# EIB64-ST4-FB-LSplit.net
KiCad netlist of a schematic drawn in EAGLE
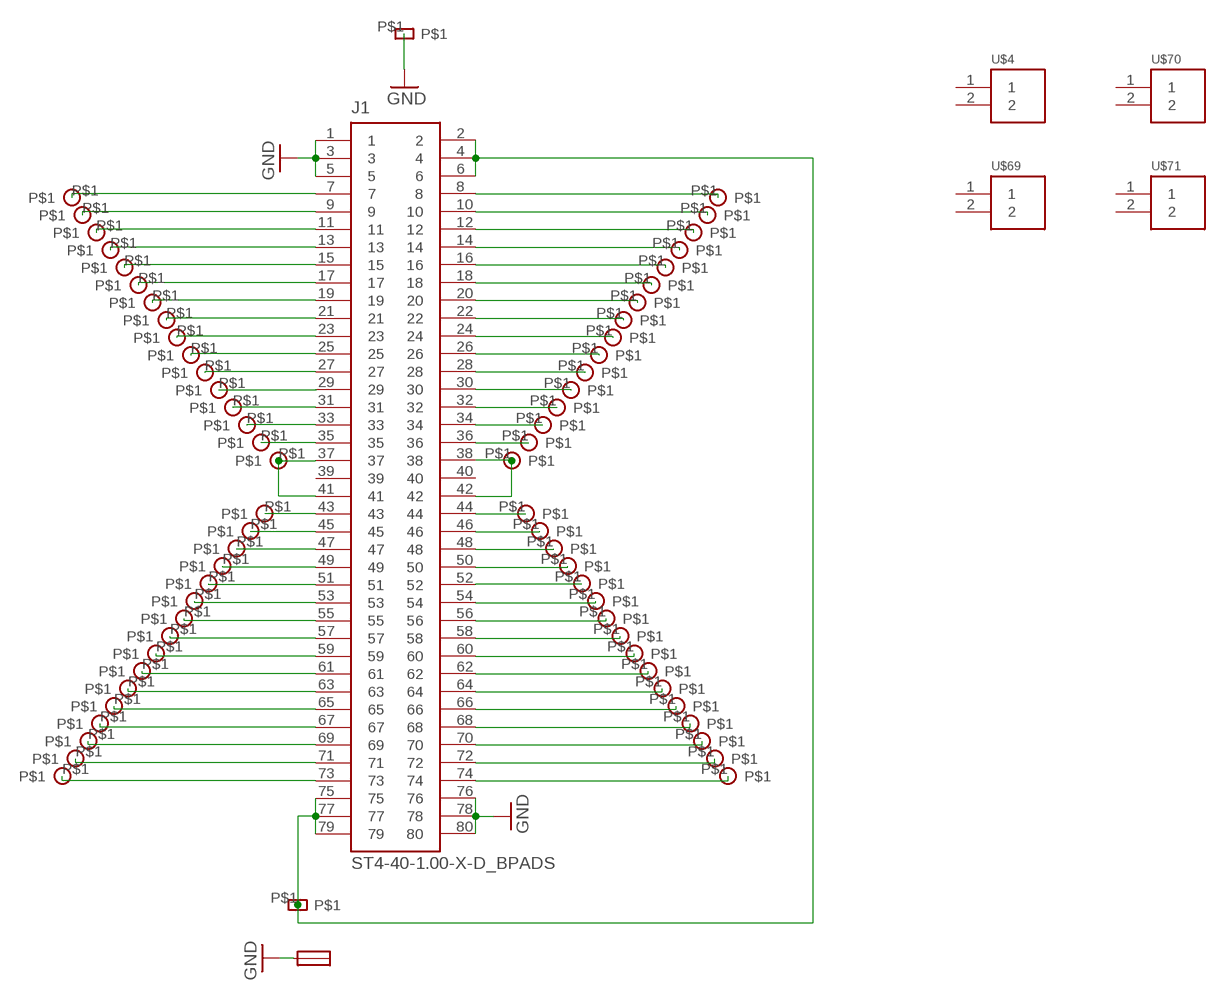
[diagram p0: schematic, sheet 1]

(export (version "E")
  (design (tool "Eeschema 10.0.6"))
  (components
    (comp (ref "J1")
      (value "ST4-40-1.00-X-D_BPADS")
      (footprint "eagle-import:ST4-40-1.00-X-D_BPADS")
      (libsource (lib "eagle-import") (part "ST4-40-1.00-X-D_BPADS"))
    )
    (comp (ref "U$1")
      (value "EIB-GND-HOLE-PAD-SMALL")
      (footprint "eagle-import:EIB-GND-HOLE-PAD-SMALL")
      (libsource (lib "eagle-import") (part "EIB-GND-HOLE-PAD-SMALL"))
    )
    (comp (ref "U$2")
      (value "JMP-PAD-SMALL")
      (footprint "eagle-import:JMP-PAD-SMALL")
      (libsource (lib "eagle-import") (part "JMP-PAD-SMALL"))
    )
    (comp (ref "U$3")
      (value "EIB-GND-HOLE-PAD-SMALL")
      (footprint "eagle-import:EIB-GND-HOLE-PAD-SMALL")
      (libsource (lib "eagle-import") (part "EIB-GND-HOLE-PAD-SMALL"))
    )
    (comp (ref "U$4")
      (value "THCONLY_TMS-102-XX-XX-S")
      (footprint "eagle-import:THCONLY_TMS-102-XX-XX-S")
      (libsource (lib "eagle-import") (part "THCONLY_TMS-102-XX-XX-S"))
    )
    (comp (ref "U$5")
      (value "EIB-TETRODE-HOLE-RS-PAD")
      (footprint "eagle-import:EIB-TETRODE-HOLE-RS-PAD")
      (libsource (lib "eagle-import") (part "EIB-TETRODE-HOLE-RS-PAD"))
    )
    (comp (ref "U$6")
      (value "EIB-TETRODE-HOLE-RS-PAD")
      (footprint "eagle-import:EIB-TETRODE-HOLE-RS-PAD")
      (libsource (lib "eagle-import") (part "EIB-TETRODE-HOLE-RS-PAD"))
    )
    (comp (ref "U$7")
      (value "EIB-TETRODE-HOLE-RS-PAD")
      (footprint "eagle-import:EIB-TETRODE-HOLE-RS-PAD")
      (libsource (lib "eagle-import") (part "EIB-TETRODE-HOLE-RS-PAD"))
    )
    (comp (ref "U$8")
      (value "EIB-TETRODE-HOLE-RS-PAD")
      (footprint "eagle-import:EIB-TETRODE-HOLE-RS-PAD")
      (libsource (lib "eagle-import") (part "EIB-TETRODE-HOLE-RS-PAD"))
    )
    (comp (ref "U$9")
      (value "EIB-TETRODE-HOLE-RS-PAD")
      (footprint "eagle-import:EIB-TETRODE-HOLE-RS-PAD")
      (libsource (lib "eagle-import") (part "EIB-TETRODE-HOLE-RS-PAD"))
    )
    (comp (ref "U$10")
      (value "EIB-TETRODE-HOLE-RS-PAD")
      (footprint "eagle-import:EIB-TETRODE-HOLE-RS-PAD")
      (libsource (lib "eagle-import") (part "EIB-TETRODE-HOLE-RS-PAD"))
    )
    (comp (ref "U$11")
      (value "EIB-TETRODE-HOLE-RS-PAD")
      (footprint "eagle-import:EIB-TETRODE-HOLE-RS-PAD")
      (libsource (lib "eagle-import") (part "EIB-TETRODE-HOLE-RS-PAD"))
    )
    (comp (ref "U$12")
      (value "EIB-TETRODE-HOLE-RS-PAD")
      (footprint "eagle-import:EIB-TETRODE-HOLE-RS-PAD")
      (libsource (lib "eagle-import") (part "EIB-TETRODE-HOLE-RS-PAD"))
    )
    (comp (ref "U$13")
      (value "EIB-TETRODE-HOLE-RS-PAD")
      (footprint "eagle-import:EIB-TETRODE-HOLE-RS-PAD")
      (libsource (lib "eagle-import") (part "EIB-TETRODE-HOLE-RS-PAD"))
    )
    (comp (ref "U$14")
      (value "EIB-TETRODE-HOLE-RS-PAD")
      (footprint "eagle-import:EIB-TETRODE-HOLE-RS-PAD")
      (libsource (lib "eagle-import") (part "EIB-TETRODE-HOLE-RS-PAD"))
    )
    (comp (ref "U$15")
      (value "EIB-TETRODE-HOLE-RS-PAD")
      (footprint "eagle-import:EIB-TETRODE-HOLE-RS-PAD")
      (libsource (lib "eagle-import") (part "EIB-TETRODE-HOLE-RS-PAD"))
    )
    (comp (ref "U$16")
      (value "EIB-TETRODE-HOLE-RS-PAD")
      (footprint "eagle-import:EIB-TETRODE-HOLE-RS-PAD")
      (libsource (lib "eagle-import") (part "EIB-TETRODE-HOLE-RS-PAD"))
    )
    (comp (ref "U$17")
      (value "EIB-TETRODE-HOLE-RS-PAD")
      (footprint "eagle-import:EIB-TETRODE-HOLE-RS-PAD")
      (libsource (lib "eagle-import") (part "EIB-TETRODE-HOLE-RS-PAD"))
    )
    (comp (ref "U$18")
      (value "EIB-TETRODE-HOLE-RS-PAD")
      (footprint "eagle-import:EIB-TETRODE-HOLE-RS-PAD")
      (libsource (lib "eagle-import") (part "EIB-TETRODE-HOLE-RS-PAD"))
    )
    (comp (ref "U$19")
      (value "EIB-TETRODE-HOLE-RS-PAD")
      (footprint "eagle-import:EIB-TETRODE-HOLE-RS-PAD")
      (libsource (lib "eagle-import") (part "EIB-TETRODE-HOLE-RS-PAD"))
    )
    (comp (ref "U$20")
      (value "EIB-TETRODE-HOLE-RS-PAD")
      (footprint "eagle-import:EIB-TETRODE-HOLE-RS-PAD")
      (libsource (lib "eagle-import") (part "EIB-TETRODE-HOLE-RS-PAD"))
    )
    (comp (ref "U$21")
      (value "EIB-TETRODE-HOLE-RS-PAD")
      (footprint "eagle-import:EIB-TETRODE-HOLE-RS-PAD")
      (libsource (lib "eagle-import") (part "EIB-TETRODE-HOLE-RS-PAD"))
    )
    (comp (ref "U$22")
      (value "EIB-TETRODE-HOLE-RS-PAD")
      (footprint "eagle-import:EIB-TETRODE-HOLE-RS-PAD")
      (libsource (lib "eagle-import") (part "EIB-TETRODE-HOLE-RS-PAD"))
    )
    (comp (ref "U$23")
      (value "EIB-TETRODE-HOLE-RS-PAD")
      (footprint "eagle-import:EIB-TETRODE-HOLE-RS-PAD")
      (libsource (lib "eagle-import") (part "EIB-TETRODE-HOLE-RS-PAD"))
    )
    (comp (ref "U$24")
      (value "EIB-TETRODE-HOLE-RS-PAD")
      (footprint "eagle-import:EIB-TETRODE-HOLE-RS-PAD")
      (libsource (lib "eagle-import") (part "EIB-TETRODE-HOLE-RS-PAD"))
    )
    (comp (ref "U$25")
      (value "EIB-TETRODE-HOLE-RS-PAD")
      (footprint "eagle-import:EIB-TETRODE-HOLE-RS-PAD")
      (libsource (lib "eagle-import") (part "EIB-TETRODE-HOLE-RS-PAD"))
    )
    (comp (ref "U$26")
      (value "EIB-TETRODE-HOLE-RS-PAD")
      (footprint "eagle-import:EIB-TETRODE-HOLE-RS-PAD")
      (libsource (lib "eagle-import") (part "EIB-TETRODE-HOLE-RS-PAD"))
    )
    (comp (ref "U$27")
      (value "EIB-TETRODE-HOLE-RS-PAD")
      (footprint "eagle-import:EIB-TETRODE-HOLE-RS-PAD")
      (libsource (lib "eagle-import") (part "EIB-TETRODE-HOLE-RS-PAD"))
    )
    (comp (ref "U$28")
      (value "EIB-TETRODE-HOLE-RS-PAD")
      (footprint "eagle-import:EIB-TETRODE-HOLE-RS-PAD")
      (libsource (lib "eagle-import") (part "EIB-TETRODE-HOLE-RS-PAD"))
    )
    (comp (ref "U$29")
      (value "EIB-TETRODE-HOLE-RS-PAD")
      (footprint "eagle-import:EIB-TETRODE-HOLE-RS-PAD")
      (libsource (lib "eagle-import") (part "EIB-TETRODE-HOLE-RS-PAD"))
    )
    (comp (ref "U$30")
      (value "EIB-TETRODE-HOLE-RS-PAD")
      (footprint "eagle-import:EIB-TETRODE-HOLE-RS-PAD")
      (libsource (lib "eagle-import") (part "EIB-TETRODE-HOLE-RS-PAD"))
    )
    (comp (ref "U$31")
      (value "EIB-TETRODE-HOLE-RS-PAD")
      (footprint "eagle-import:EIB-TETRODE-HOLE-RS-PAD")
      (libsource (lib "eagle-import") (part "EIB-TETRODE-HOLE-RS-PAD"))
    )
    (comp (ref "U$32")
      (value "EIB-TETRODE-HOLE-RS-PAD")
      (footprint "eagle-import:EIB-TETRODE-HOLE-RS-PAD")
      (libsource (lib "eagle-import") (part "EIB-TETRODE-HOLE-RS-PAD"))
    )
    (comp (ref "U$33")
      (value "EIB-TETRODE-HOLE-RS-PAD")
      (footprint "eagle-import:EIB-TETRODE-HOLE-RS-PAD")
      (libsource (lib "eagle-import") (part "EIB-TETRODE-HOLE-RS-PAD"))
    )
    (comp (ref "U$34")
      (value "EIB-TETRODE-HOLE-RS-PAD")
      (footprint "eagle-import:EIB-TETRODE-HOLE-RS-PAD")
      (libsource (lib "eagle-import") (part "EIB-TETRODE-HOLE-RS-PAD"))
    )
    (comp (ref "U$35")
      (value "EIB-TETRODE-HOLE-RS-PAD")
      (footprint "eagle-import:EIB-TETRODE-HOLE-RS-PAD")
      (libsource (lib "eagle-import") (part "EIB-TETRODE-HOLE-RS-PAD"))
    )
    (comp (ref "U$36")
      (value "EIB-TETRODE-HOLE-RS-PAD")
      (footprint "eagle-import:EIB-TETRODE-HOLE-RS-PAD")
      (libsource (lib "eagle-import") (part "EIB-TETRODE-HOLE-RS-PAD"))
    )
    (comp (ref "U$37")
      (value "EIB-TETRODE-HOLE-RS-PAD")
      (footprint "eagle-import:EIB-TETRODE-HOLE-RS-PAD")
      (libsource (lib "eagle-import") (part "EIB-TETRODE-HOLE-RS-PAD"))
    )
    (comp (ref "U$38")
      (value "EIB-TETRODE-HOLE-RS-PAD")
      (footprint "eagle-import:EIB-TETRODE-HOLE-RS-PAD")
      (libsource (lib "eagle-import") (part "EIB-TETRODE-HOLE-RS-PAD"))
    )
    (comp (ref "U$39")
      (value "EIB-TETRODE-HOLE-RS-PAD")
      (footprint "eagle-import:EIB-TETRODE-HOLE-RS-PAD")
      (libsource (lib "eagle-import") (part "EIB-TETRODE-HOLE-RS-PAD"))
    )
    (comp (ref "U$40")
      (value "EIB-TETRODE-HOLE-RS-PAD")
      (footprint "eagle-import:EIB-TETRODE-HOLE-RS-PAD")
      (libsource (lib "eagle-import") (part "EIB-TETRODE-HOLE-RS-PAD"))
    )
    (comp (ref "U$41")
      (value "EIB-TETRODE-HOLE-RS-PAD")
      (footprint "eagle-import:EIB-TETRODE-HOLE-RS-PAD")
      (libsource (lib "eagle-import") (part "EIB-TETRODE-HOLE-RS-PAD"))
    )
    (comp (ref "U$42")
      (value "EIB-TETRODE-HOLE-RS-PAD")
      (footprint "eagle-import:EIB-TETRODE-HOLE-RS-PAD")
      (libsource (lib "eagle-import") (part "EIB-TETRODE-HOLE-RS-PAD"))
    )
    (comp (ref "U$43")
      (value "EIB-TETRODE-HOLE-RS-PAD")
      (footprint "eagle-import:EIB-TETRODE-HOLE-RS-PAD")
      (libsource (lib "eagle-import") (part "EIB-TETRODE-HOLE-RS-PAD"))
    )
    (comp (ref "U$44")
      (value "EIB-TETRODE-HOLE-RS-PAD")
      (footprint "eagle-import:EIB-TETRODE-HOLE-RS-PAD")
      (libsource (lib "eagle-import") (part "EIB-TETRODE-HOLE-RS-PAD"))
    )
    (comp (ref "U$45")
      (value "EIB-TETRODE-HOLE-RS-PAD")
      (footprint "eagle-import:EIB-TETRODE-HOLE-RS-PAD")
      (libsource (lib "eagle-import") (part "EIB-TETRODE-HOLE-RS-PAD"))
    )
    (comp (ref "U$46")
      (value "EIB-TETRODE-HOLE-RS-PAD")
      (footprint "eagle-import:EIB-TETRODE-HOLE-RS-PAD")
      (libsource (lib "eagle-import") (part "EIB-TETRODE-HOLE-RS-PAD"))
    )
    (comp (ref "U$47")
      (value "EIB-TETRODE-HOLE-RS-PAD")
      (footprint "eagle-import:EIB-TETRODE-HOLE-RS-PAD")
      (libsource (lib "eagle-import") (part "EIB-TETRODE-HOLE-RS-PAD"))
    )
    (comp (ref "U$48")
      (value "EIB-TETRODE-HOLE-RS-PAD")
      (footprint "eagle-import:EIB-TETRODE-HOLE-RS-PAD")
      (libsource (lib "eagle-import") (part "EIB-TETRODE-HOLE-RS-PAD"))
    )
    (comp (ref "U$49")
      (value "EIB-TETRODE-HOLE-RS-PAD")
      (footprint "eagle-import:EIB-TETRODE-HOLE-RS-PAD")
      (libsource (lib "eagle-import") (part "EIB-TETRODE-HOLE-RS-PAD"))
    )
    (comp (ref "U$50")
      (value "EIB-TETRODE-HOLE-RS-PAD")
      (footprint "eagle-import:EIB-TETRODE-HOLE-RS-PAD")
      (libsource (lib "eagle-import") (part "EIB-TETRODE-HOLE-RS-PAD"))
    )
    (comp (ref "U$51")
      (value "EIB-TETRODE-HOLE-RS-PAD")
      (footprint "eagle-import:EIB-TETRODE-HOLE-RS-PAD")
      (libsource (lib "eagle-import") (part "EIB-TETRODE-HOLE-RS-PAD"))
    )
    (comp (ref "U$52")
      (value "EIB-TETRODE-HOLE-RS-PAD")
      (footprint "eagle-import:EIB-TETRODE-HOLE-RS-PAD")
      (libsource (lib "eagle-import") (part "EIB-TETRODE-HOLE-RS-PAD"))
    )
    (comp (ref "U$53")
      (value "EIB-TETRODE-HOLE-RS-PAD")
      (footprint "eagle-import:EIB-TETRODE-HOLE-RS-PAD")
      (libsource (lib "eagle-import") (part "EIB-TETRODE-HOLE-RS-PAD"))
    )
    (comp (ref "U$54")
      (value "EIB-TETRODE-HOLE-RS-PAD")
      (footprint "eagle-import:EIB-TETRODE-HOLE-RS-PAD")
      (libsource (lib "eagle-import") (part "EIB-TETRODE-HOLE-RS-PAD"))
    )
    (comp (ref "U$55")
      (value "EIB-TETRODE-HOLE-RS-PAD")
      (footprint "eagle-import:EIB-TETRODE-HOLE-RS-PAD")
      (libsource (lib "eagle-import") (part "EIB-TETRODE-HOLE-RS-PAD"))
    )
    (comp (ref "U$56")
      (value "EIB-TETRODE-HOLE-RS-PAD")
      (footprint "eagle-import:EIB-TETRODE-HOLE-RS-PAD")
      (libsource (lib "eagle-import") (part "EIB-TETRODE-HOLE-RS-PAD"))
    )
    (comp (ref "U$57")
      (value "EIB-TETRODE-HOLE-RS-PAD")
      (footprint "eagle-import:EIB-TETRODE-HOLE-RS-PAD")
      (libsource (lib "eagle-import") (part "EIB-TETRODE-HOLE-RS-PAD"))
    )
    (comp (ref "U$58")
      (value "EIB-TETRODE-HOLE-RS-PAD")
      (footprint "eagle-import:EIB-TETRODE-HOLE-RS-PAD")
      (libsource (lib "eagle-import") (part "EIB-TETRODE-HOLE-RS-PAD"))
    )
    (comp (ref "U$59")
      (value "EIB-TETRODE-HOLE-RS-PAD")
      (footprint "eagle-import:EIB-TETRODE-HOLE-RS-PAD")
      (libsource (lib "eagle-import") (part "EIB-TETRODE-HOLE-RS-PAD"))
    )
    (comp (ref "U$60")
      (value "EIB-TETRODE-HOLE-RS-PAD")
      (footprint "eagle-import:EIB-TETRODE-HOLE-RS-PAD")
      (libsource (lib "eagle-import") (part "EIB-TETRODE-HOLE-RS-PAD"))
    )
    (comp (ref "U$61")
      (value "EIB-TETRODE-HOLE-RS-PAD")
      (footprint "eagle-import:EIB-TETRODE-HOLE-RS-PAD")
      (libsource (lib "eagle-import") (part "EIB-TETRODE-HOLE-RS-PAD"))
    )
    (comp (ref "U$62")
      (value "EIB-TETRODE-HOLE-RS-PAD")
      (footprint "eagle-import:EIB-TETRODE-HOLE-RS-PAD")
      (libsource (lib "eagle-import") (part "EIB-TETRODE-HOLE-RS-PAD"))
    )
    (comp (ref "U$63")
      (value "EIB-TETRODE-HOLE-RS-PAD")
      (footprint "eagle-import:EIB-TETRODE-HOLE-RS-PAD")
      (libsource (lib "eagle-import") (part "EIB-TETRODE-HOLE-RS-PAD"))
    )
    (comp (ref "U$64")
      (value "EIB-TETRODE-HOLE-RS-PAD")
      (footprint "eagle-import:EIB-TETRODE-HOLE-RS-PAD")
      (libsource (lib "eagle-import") (part "EIB-TETRODE-HOLE-RS-PAD"))
    )
    (comp (ref "U$65")
      (value "EIB-TETRODE-HOLE-RS-PAD")
      (footprint "eagle-import:EIB-TETRODE-HOLE-RS-PAD")
      (libsource (lib "eagle-import") (part "EIB-TETRODE-HOLE-RS-PAD"))
    )
    (comp (ref "U$66")
      (value "EIB-TETRODE-HOLE-RS-PAD")
      (footprint "eagle-import:EIB-TETRODE-HOLE-RS-PAD")
      (libsource (lib "eagle-import") (part "EIB-TETRODE-HOLE-RS-PAD"))
    )
    (comp (ref "U$67")
      (value "EIB-TETRODE-HOLE-RS-PAD")
      (footprint "eagle-import:EIB-TETRODE-HOLE-RS-PAD")
      (libsource (lib "eagle-import") (part "EIB-TETRODE-HOLE-RS-PAD"))
    )
    (comp (ref "U$68")
      (value "EIB-TETRODE-HOLE-RS-PAD")
      (footprint "eagle-import:EIB-TETRODE-HOLE-RS-PAD")
      (libsource (lib "eagle-import") (part "EIB-TETRODE-HOLE-RS-PAD"))
    )
    (comp (ref "U$69")
      (value "THCONLY_TMS-102-XX-XX-S")
      (footprint "eagle-import:THCONLY_TMS-102-XX-XX-S")
      (libsource (lib "eagle-import") (part "THCONLY_TMS-102-XX-XX-S"))
    )
    (comp (ref "U$70")
      (value "THCONLY_TMS-102-XX-XX-S")
      (footprint "eagle-import:THCONLY_TMS-102-XX-XX-S")
      (libsource (lib "eagle-import") (part "THCONLY_TMS-102-XX-XX-S"))
    )
    (comp (ref "U$71")
      (value "THCONLY_TMS-102-XX-XX-S")
      (footprint "eagle-import:THCONLY_TMS-102-XX-XX-S")
      (libsource (lib "eagle-import") (part "THCONLY_TMS-102-XX-XX-S"))
    )
  )
  (nets
    (net (code "1") (name "GND") (class "Default")
      (node (ref "J1") (pin "1") (pinfunction "1_1") (pintype "bidirectional"))
      (node (ref "J1") (pin "3") (pinfunction "3_3") (pintype "bidirectional"))
      (node (ref "J1") (pin "5") (pinfunction "5_5") (pintype "bidirectional"))
      (node (ref "J1") (pin "76") (pinfunction "76_76") (pintype "bidirectional"))
      (node (ref "J1") (pin "78") (pinfunction "78_78") (pintype "bidirectional"))
      (node (ref "J1") (pin "80") (pinfunction "80_80") (pintype "bidirectional"))
      (node (ref "U$1") (pin "P$1") (pinfunction "P$1_P$1") (pintype "bidirectional"))
      (node (ref "U$2") (pin "P$1") (pinfunction "P$1_P$1") (pintype "bidirectional"))
    )
    (net (code "2") (name "Net-(J1-Pad2)") (class "Default")
      (node (ref "J1") (pin "2") (pinfunction "2_2") (pintype "bidirectional"))
      (node (ref "J1") (pin "4") (pinfunction "4_4") (pintype "bidirectional"))
      (node (ref "J1") (pin "6") (pinfunction "6_6") (pintype "bidirectional"))
      (node (ref "J1") (pin "75") (pinfunction "75_75") (pintype "bidirectional"))
      (node (ref "J1") (pin "77") (pinfunction "77_77") (pintype "bidirectional"))
      (node (ref "J1") (pin "79") (pinfunction "79_79") (pintype "bidirectional"))
      (node (ref "U$3") (pin "P$1") (pinfunction "P$1_P$1") (pintype "bidirectional"))
    )
    (net (code "3") (name "Net-(J1-Pad7)") (class "Default")
      (node (ref "J1") (pin "7") (pinfunction "7_7") (pintype "bidirectional"))
      (node (ref "U$36") (pin "P$1") (pinfunction "P$1_P$1") (pintype "bidirectional"))
    )
    (net (code "4") (name "Net-(J1-Pad8)") (class "Default")
      (node (ref "J1") (pin "8") (pinfunction "8_8") (pintype "bidirectional"))
      (node (ref "U$22") (pin "P$1") (pinfunction "P$1_P$1") (pintype "bidirectional"))
    )
    (net (code "5") (name "Net-(J1-Pad9)") (class "Default")
      (node (ref "J1") (pin "9") (pinfunction "9_9") (pintype "bidirectional"))
      (node (ref "U$35") (pin "P$1") (pinfunction "P$1_P$1") (pintype "bidirectional"))
    )
    (net (code "6") (name "Net-(J1-Pad10)") (class "Default")
      (node (ref "J1") (pin "10") (pinfunction "10_10") (pintype "bidirectional"))
      (node (ref "U$21") (pin "P$1") (pinfunction "P$1_P$1") (pintype "bidirectional"))
    )
    (net (code "7") (name "Net-(J1-Pad11)") (class "Default")
      (node (ref "J1") (pin "11") (pinfunction "11_11") (pintype "bidirectional"))
      (node (ref "U$34") (pin "P$1") (pinfunction "P$1_P$1") (pintype "bidirectional"))
    )
    (net (code "8") (name "Net-(J1-Pad12)") (class "Default")
      (node (ref "J1") (pin "12") (pinfunction "12_12") (pintype "bidirectional"))
      (node (ref "U$20") (pin "P$1") (pinfunction "P$1_P$1") (pintype "bidirectional"))
    )
    (net (code "9") (name "Net-(J1-Pad13)") (class "Default")
      (node (ref "J1") (pin "13") (pinfunction "13_13") (pintype "bidirectional"))
      (node (ref "U$33") (pin "P$1") (pinfunction "P$1_P$1") (pintype "bidirectional"))
    )
    (net (code "10") (name "Net-(J1-Pad14)") (class "Default")
      (node (ref "J1") (pin "14") (pinfunction "14_14") (pintype "bidirectional"))
      (node (ref "U$19") (pin "P$1") (pinfunction "P$1_P$1") (pintype "bidirectional"))
    )
    (net (code "11") (name "Net-(J1-Pad15)") (class "Default")
      (node (ref "J1") (pin "15") (pinfunction "15_15") (pintype "bidirectional"))
      (node (ref "U$32") (pin "P$1") (pinfunction "P$1_P$1") (pintype "bidirectional"))
    )
    (net (code "12") (name "Net-(J1-Pad16)") (class "Default")
      (node (ref "J1") (pin "16") (pinfunction "16_16") (pintype "bidirectional"))
      (node (ref "U$18") (pin "P$1") (pinfunction "P$1_P$1") (pintype "bidirectional"))
    )
    (net (code "13") (name "Net-(J1-Pad17)") (class "Default")
      (node (ref "J1") (pin "17") (pinfunction "17_17") (pintype "bidirectional"))
      (node (ref "U$31") (pin "P$1") (pinfunction "P$1_P$1") (pintype "bidirectional"))
    )
    (net (code "14") (name "Net-(J1-Pad18)") (class "Default")
      (node (ref "J1") (pin "18") (pinfunction "18_18") (pintype "bidirectional"))
      (node (ref "U$17") (pin "P$1") (pinfunction "P$1_P$1") (pintype "bidirectional"))
    )
    (net (code "15") (name "Net-(J1-Pad19)") (class "Default")
      (node (ref "J1") (pin "19") (pinfunction "19_19") (pintype "bidirectional"))
      (node (ref "U$30") (pin "P$1") (pinfunction "P$1_P$1") (pintype "bidirectional"))
    )
    (net (code "16") (name "Net-(J1-Pad20)") (class "Default")
      (node (ref "J1") (pin "20") (pinfunction "20_20") (pintype "bidirectional"))
      (node (ref "U$16") (pin "P$1") (pinfunction "P$1_P$1") (pintype "bidirectional"))
    )
    (net (code "17") (name "Net-(J1-Pad21)") (class "Default")
      (node (ref "J1") (pin "21") (pinfunction "21_21") (pintype "bidirectional"))
      (node (ref "U$29") (pin "P$1") (pinfunction "P$1_P$1") (pintype "bidirectional"))
    )
    (net (code "18") (name "Net-(J1-Pad22)") (class "Default")
      (node (ref "J1") (pin "22") (pinfunction "22_22") (pintype "bidirectional"))
      (node (ref "U$15") (pin "P$1") (pinfunction "P$1_P$1") (pintype "bidirectional"))
    )
    (net (code "19") (name "Net-(J1-Pad23)") (class "Default")
      (node (ref "J1") (pin "23") (pinfunction "23_23") (pintype "bidirectional"))
      (node (ref "U$28") (pin "P$1") (pinfunction "P$1_P$1") (pintype "bidirectional"))
    )
    (net (code "20") (name "Net-(J1-Pad24)") (class "Default")
      (node (ref "J1") (pin "24") (pinfunction "24_24") (pintype "bidirectional"))
      (node (ref "U$14") (pin "P$1") (pinfunction "P$1_P$1") (pintype "bidirectional"))
    )
    (net (code "21") (name "Net-(J1-Pad25)") (class "Default")
      (node (ref "J1") (pin "25") (pinfunction "25_25") (pintype "bidirectional"))
      (node (ref "U$27") (pin "P$1") (pinfunction "P$1_P$1") (pintype "bidirectional"))
    )
    (net (code "22") (name "Net-(J1-Pad26)") (class "Default")
      (node (ref "J1") (pin "26") (pinfunction "26_26") (pintype "bidirectional"))
      (node (ref "U$13") (pin "P$1") (pinfunction "P$1_P$1") (pintype "bidirectional"))
    )
    (net (code "23") (name "Net-(J1-Pad27)") (class "Default")
      (node (ref "J1") (pin "27") (pinfunction "27_27") (pintype "bidirectional"))
      (node (ref "U$26") (pin "P$1") (pinfunction "P$1_P$1") (pintype "bidirectional"))
    )
    (net (code "24") (name "Net-(J1-Pad28)") (class "Default")
      (node (ref "J1") (pin "28") (pinfunction "28_28") (pintype "bidirectional"))
      (node (ref "U$12") (pin "P$1") (pinfunction "P$1_P$1") (pintype "bidirectional"))
    )
    (net (code "25") (name "Net-(J1-Pad29)") (class "Default")
      (node (ref "J1") (pin "29") (pinfunction "29_29") (pintype "bidirectional"))
      (node (ref "U$25") (pin "P$1") (pinfunction "P$1_P$1") (pintype "bidirectional"))
    )
    (net (code "26") (name "Net-(J1-Pad30)") (class "Default")
      (node (ref "J1") (pin "30") (pinfunction "30_30") (pintype "bidirectional"))
      (node (ref "U$11") (pin "P$1") (pinfunction "P$1_P$1") (pintype "bidirectional"))
    )
    (net (code "27") (name "Net-(J1-Pad31)") (class "Default")
      (node (ref "J1") (pin "31") (pinfunction "31_31") (pintype "bidirectional"))
      (node (ref "U$24") (pin "P$1") (pinfunction "P$1_P$1") (pintype "bidirectional"))
    )
    (net (code "28") (name "Net-(J1-Pad32)") (class "Default")
      (node (ref "J1") (pin "32") (pinfunction "32_32") (pintype "bidirectional"))
      (node (ref "U$10") (pin "P$1") (pinfunction "P$1_P$1") (pintype "bidirectional"))
    )
    (net (code "29") (name "Net-(J1-Pad33)") (class "Default")
      (node (ref "J1") (pin "33") (pinfunction "33_33") (pintype "bidirectional"))
      (node (ref "U$23") (pin "P$1") (pinfunction "P$1_P$1") (pintype "bidirectional"))
    )
    (net (code "30") (name "Net-(J1-Pad34)") (class "Default")
      (node (ref "J1") (pin "34") (pinfunction "34_34") (pintype "bidirectional"))
      (node (ref "U$9") (pin "P$1") (pinfunction "P$1_P$1") (pintype "bidirectional"))
    )
    (net (code "31") (name "Net-(J1-Pad35)") (class "Default")
      (node (ref "J1") (pin "35") (pinfunction "35_35") (pintype "bidirectional"))
      (node (ref "U$7") (pin "P$1") (pinfunction "P$1_P$1") (pintype "bidirectional"))
    )
    (net (code "32") (name "Net-(J1-Pad36)") (class "Default")
      (node (ref "J1") (pin "36") (pinfunction "36_36") (pintype "bidirectional"))
      (node (ref "U$5") (pin "P$1") (pinfunction "P$1_P$1") (pintype "bidirectional"))
    )
    (net (code "33") (name "Net-(J1-Pad37)") (class "Default")
      (node (ref "J1") (pin "37") (pinfunction "37_37") (pintype "bidirectional"))
      (node (ref "J1") (pin "41") (pinfunction "41_41") (pintype "bidirectional"))
      (node (ref "U$8") (pin "P$1") (pinfunction "P$1_P$1") (pintype "bidirectional"))
    )
    (net (code "34") (name "Net-(J1-Pad38)") (class "Default")
      (node (ref "J1") (pin "38") (pinfunction "38_38") (pintype "bidirectional"))
      (node (ref "J1") (pin "42") (pinfunction "42_42") (pintype "bidirectional"))
      (node (ref "U$6") (pin "P$1") (pinfunction "P$1_P$1") (pintype "bidirectional"))
    )
    (net (code "35") (name "Net-(J1-Pad43)") (class "Default")
      (node (ref "J1") (pin "43") (pinfunction "43_43") (pintype "bidirectional"))
      (node (ref "U$53") (pin "P$1") (pinfunction "P$1_P$1") (pintype "bidirectional"))
    )
    (net (code "36") (name "Net-(J1-Pad44)") (class "Default")
      (node (ref "J1") (pin "44") (pinfunction "44_44") (pintype "bidirectional"))
      (node (ref "U$37") (pin "P$1") (pinfunction "P$1_P$1") (pintype "bidirectional"))
    )
    (net (code "37") (name "Net-(J1-Pad45)") (class "Default")
      (node (ref "J1") (pin "45") (pinfunction "45_45") (pintype "bidirectional"))
      (node (ref "U$54") (pin "P$1") (pinfunction "P$1_P$1") (pintype "bidirectional"))
    )
    (net (code "38") (name "Net-(J1-Pad46)") (class "Default")
      (node (ref "J1") (pin "46") (pinfunction "46_46") (pintype "bidirectional"))
      (node (ref "U$38") (pin "P$1") (pinfunction "P$1_P$1") (pintype "bidirectional"))
    )
    (net (code "39") (name "Net-(J1-Pad47)") (class "Default")
      (node (ref "J1") (pin "47") (pinfunction "47_47") (pintype "bidirectional"))
      (node (ref "U$55") (pin "P$1") (pinfunction "P$1_P$1") (pintype "bidirectional"))
    )
    (net (code "40") (name "Net-(J1-Pad48)") (class "Default")
      (node (ref "J1") (pin "48") (pinfunction "48_48") (pintype "bidirectional"))
      (node (ref "U$39") (pin "P$1") (pinfunction "P$1_P$1") (pintype "bidirectional"))
    )
    (net (code "41") (name "Net-(J1-Pad49)") (class "Default")
      (node (ref "J1") (pin "49") (pinfunction "49_49") (pintype "bidirectional"))
      (node (ref "U$56") (pin "P$1") (pinfunction "P$1_P$1") (pintype "bidirectional"))
    )
    (net (code "42") (name "Net-(J1-Pad50)") (class "Default")
      (node (ref "J1") (pin "50") (pinfunction "50_50") (pintype "bidirectional"))
      (node (ref "U$40") (pin "P$1") (pinfunction "P$1_P$1") (pintype "bidirectional"))
    )
    (net (code "43") (name "Net-(J1-Pad51)") (class "Default")
      (node (ref "J1") (pin "51") (pinfunction "51_51") (pintype "bidirectional"))
      (node (ref "U$57") (pin "P$1") (pinfunction "P$1_P$1") (pintype "bidirectional"))
    )
    (net (code "44") (name "Net-(J1-Pad52)") (class "Default")
      (node (ref "J1") (pin "52") (pinfunction "52_52") (pintype "bidirectional"))
      (node (ref "U$41") (pin "P$1") (pinfunction "P$1_P$1") (pintype "bidirectional"))
    )
    (net (code "45") (name "Net-(J1-Pad53)") (class "Default")
      (node (ref "J1") (pin "53") (pinfunction "53_53") (pintype "bidirectional"))
      (node (ref "U$58") (pin "P$1") (pinfunction "P$1_P$1") (pintype "bidirectional"))
    )
    (net (code "46") (name "Net-(J1-Pad54)") (class "Default")
      (node (ref "J1") (pin "54") (pinfunction "54_54") (pintype "bidirectional"))
      (node (ref "U$42") (pin "P$1") (pinfunction "P$1_P$1") (pintype "bidirectional"))
    )
    (net (code "47") (name "Net-(J1-Pad55)") (class "Default")
      (node (ref "J1") (pin "55") (pinfunction "55_55") (pintype "bidirectional"))
      (node (ref "U$59") (pin "P$1") (pinfunction "P$1_P$1") (pintype "bidirectional"))
    )
    (net (code "48") (name "Net-(J1-Pad56)") (class "Default")
      (node (ref "J1") (pin "56") (pinfunction "56_56") (pintype "bidirectional"))
      (node (ref "U$43") (pin "P$1") (pinfunction "P$1_P$1") (pintype "bidirectional"))
    )
    (net (code "49") (name "Net-(J1-Pad57)") (class "Default")
      (node (ref "J1") (pin "57") (pinfunction "57_57") (pintype "bidirectional"))
      (node (ref "U$60") (pin "P$1") (pinfunction "P$1_P$1") (pintype "bidirectional"))
    )
    (net (code "50") (name "Net-(J1-Pad58)") (class "Default")
      (node (ref "J1") (pin "58") (pinfunction "58_58") (pintype "bidirectional"))
      (node (ref "U$44") (pin "P$1") (pinfunction "P$1_P$1") (pintype "bidirectional"))
    )
    (net (code "51") (name "Net-(J1-Pad59)") (class "Default")
      (node (ref "J1") (pin "59") (pinfunction "59_59") (pintype "bidirectional"))
      (node (ref "U$61") (pin "P$1") (pinfunction "P$1_P$1") (pintype "bidirectional"))
    )
    (net (code "52") (name "Net-(J1-Pad60)") (class "Default")
      (node (ref "J1") (pin "60") (pinfunction "60_60") (pintype "bidirectional"))
      (node (ref "U$45") (pin "P$1") (pinfunction "P$1_P$1") (pintype "bidirectional"))
    )
    (net (code "53") (name "Net-(J1-Pad61)") (class "Default")
      (node (ref "J1") (pin "61") (pinfunction "61_61") (pintype "bidirectional"))
      (node (ref "U$62") (pin "P$1") (pinfunction "P$1_P$1") (pintype "bidirectional"))
    )
    (net (code "54") (name "Net-(J1-Pad62)") (class "Default")
      (node (ref "J1") (pin "62") (pinfunction "62_62") (pintype "bidirectional"))
      (node (ref "U$46") (pin "P$1") (pinfunction "P$1_P$1") (pintype "bidirectional"))
    )
    (net (code "55") (name "Net-(J1-Pad63)") (class "Default")
      (node (ref "J1") (pin "63") (pinfunction "63_63") (pintype "bidirectional"))
      (node (ref "U$63") (pin "P$1") (pinfunction "P$1_P$1") (pintype "bidirectional"))
    )
    (net (code "56") (name "Net-(J1-Pad64)") (class "Default")
      (node (ref "J1") (pin "64") (pinfunction "64_64") (pintype "bidirectional"))
      (node (ref "U$47") (pin "P$1") (pinfunction "P$1_P$1") (pintype "bidirectional"))
    )
    (net (code "57") (name "Net-(J1-Pad65)") (class "Default")
      (node (ref "J1") (pin "65") (pinfunction "65_65") (pintype "bidirectional"))
      (node (ref "U$64") (pin "P$1") (pinfunction "P$1_P$1") (pintype "bidirectional"))
    )
    (net (code "58") (name "Net-(J1-Pad66)") (class "Default")
      (node (ref "J1") (pin "66") (pinfunction "66_66") (pintype "bidirectional"))
      (node (ref "U$48") (pin "P$1") (pinfunction "P$1_P$1") (pintype "bidirectional"))
    )
    (net (code "59") (name "Net-(J1-Pad67)") (class "Default")
      (node (ref "J1") (pin "67") (pinfunction "67_67") (pintype "bidirectional"))
      (node (ref "U$65") (pin "P$1") (pinfunction "P$1_P$1") (pintype "bidirectional"))
    )
    (net (code "60") (name "Net-(J1-Pad68)") (class "Default")
      (node (ref "J1") (pin "68") (pinfunction "68_68") (pintype "bidirectional"))
      (node (ref "U$49") (pin "P$1") (pinfunction "P$1_P$1") (pintype "bidirectional"))
    )
    (net (code "61") (name "Net-(J1-Pad69)") (class "Default")
      (node (ref "J1") (pin "69") (pinfunction "69_69") (pintype "bidirectional"))
      (node (ref "U$66") (pin "P$1") (pinfunction "P$1_P$1") (pintype "bidirectional"))
    )
    (net (code "62") (name "Net-(J1-Pad70)") (class "Default")
      (node (ref "J1") (pin "70") (pinfunction "70_70") (pintype "bidirectional"))
      (node (ref "U$50") (pin "P$1") (pinfunction "P$1_P$1") (pintype "bidirectional"))
    )
    (net (code "63") (name "Net-(J1-Pad71)") (class "Default")
      (node (ref "J1") (pin "71") (pinfunction "71_71") (pintype "bidirectional"))
      (node (ref "U$67") (pin "P$1") (pinfunction "P$1_P$1") (pintype "bidirectional"))
    )
    (net (code "64") (name "Net-(J1-Pad72)") (class "Default")
      (node (ref "J1") (pin "72") (pinfunction "72_72") (pintype "bidirectional"))
      (node (ref "U$51") (pin "P$1") (pinfunction "P$1_P$1") (pintype "bidirectional"))
    )
    (net (code "65") (name "Net-(J1-Pad73)") (class "Default")
      (node (ref "J1") (pin "73") (pinfunction "73_73") (pintype "bidirectional"))
      (node (ref "U$68") (pin "P$1") (pinfunction "P$1_P$1") (pintype "bidirectional"))
    )
    (net (code "66") (name "Net-(J1-Pad74)") (class "Default")
      (node (ref "J1") (pin "74") (pinfunction "74_74") (pintype "bidirectional"))
      (node (ref "U$52") (pin "P$1") (pinfunction "P$1_P$1") (pintype "bidirectional"))
    )
    (net (code "67") (name "unconnected-(J1-Pad39)") (class "Default")
      (node (ref "J1") (pin "39") (pinfunction "39_39") (pintype "bidirectional"))
    )
    (net (code "68") (name "unconnected-(J1-Pad40)") (class "Default")
      (node (ref "J1") (pin "40") (pinfunction "40_40") (pintype "bidirectional"))
    )
    (net (code "69") (name "unconnected-(U$4-Pad1)") (class "Default")
      (node (ref "U$4") (pin "1") (pinfunction "1_1") (pintype "bidirectional"))
    )
    (net (code "70") (name "unconnected-(U$4-Pad2)") (class "Default")
      (node (ref "U$4") (pin "2") (pinfunction "2_2") (pintype "bidirectional"))
    )
    (net (code "71") (name "unconnected-(U$69-Pad1)") (class "Default")
      (node (ref "U$69") (pin "1") (pinfunction "1_1") (pintype "bidirectional"))
    )
    (net (code "72") (name "unconnected-(U$69-Pad2)") (class "Default")
      (node (ref "U$69") (pin "2") (pinfunction "2_2") (pintype "bidirectional"))
    )
    (net (code "73") (name "unconnected-(U$70-Pad1)") (class "Default")
      (node (ref "U$70") (pin "1") (pinfunction "1_1") (pintype "bidirectional"))
    )
    (net (code "74") (name "unconnected-(U$70-Pad2)") (class "Default")
      (node (ref "U$70") (pin "2") (pinfunction "2_2") (pintype "bidirectional"))
    )
    (net (code "75") (name "unconnected-(U$71-Pad1)") (class "Default")
      (node (ref "U$71") (pin "1") (pinfunction "1_1") (pintype "bidirectional"))
    )
    (net (code "76") (name "unconnected-(U$71-Pad2)") (class "Default")
      (node (ref "U$71") (pin "2") (pinfunction "2_2") (pintype "bidirectional"))
    )
  )
)
